# Seeeduino-Stalker-v3_0.net
KiCad netlist of a schematic drawn in EAGLE
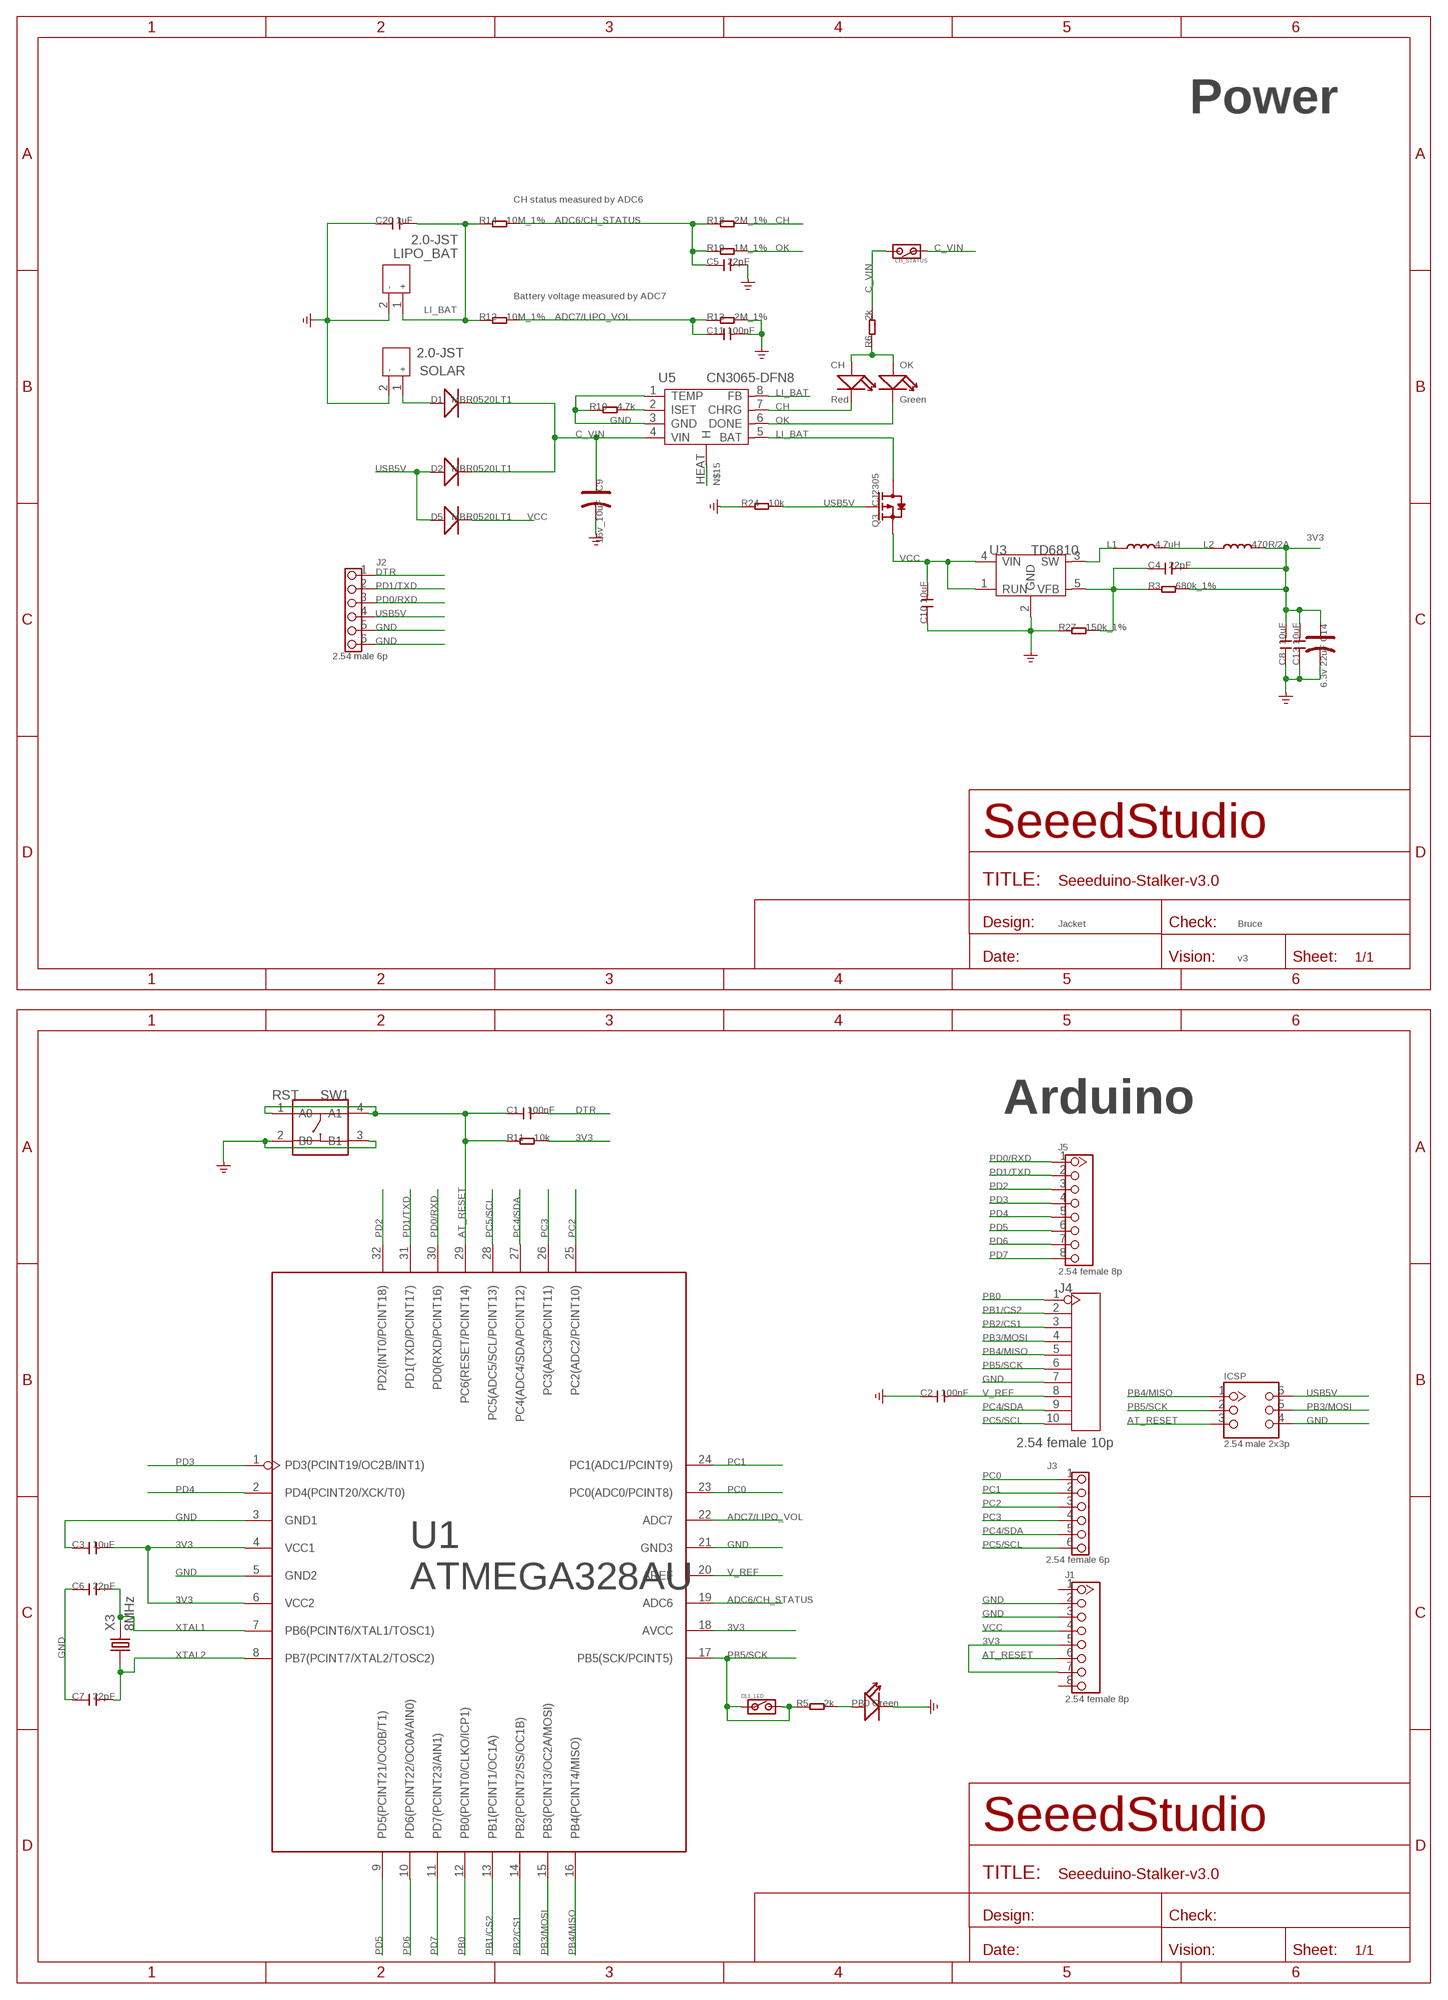
[diagram p0: schematic, sheet 1, part 1 of 2]
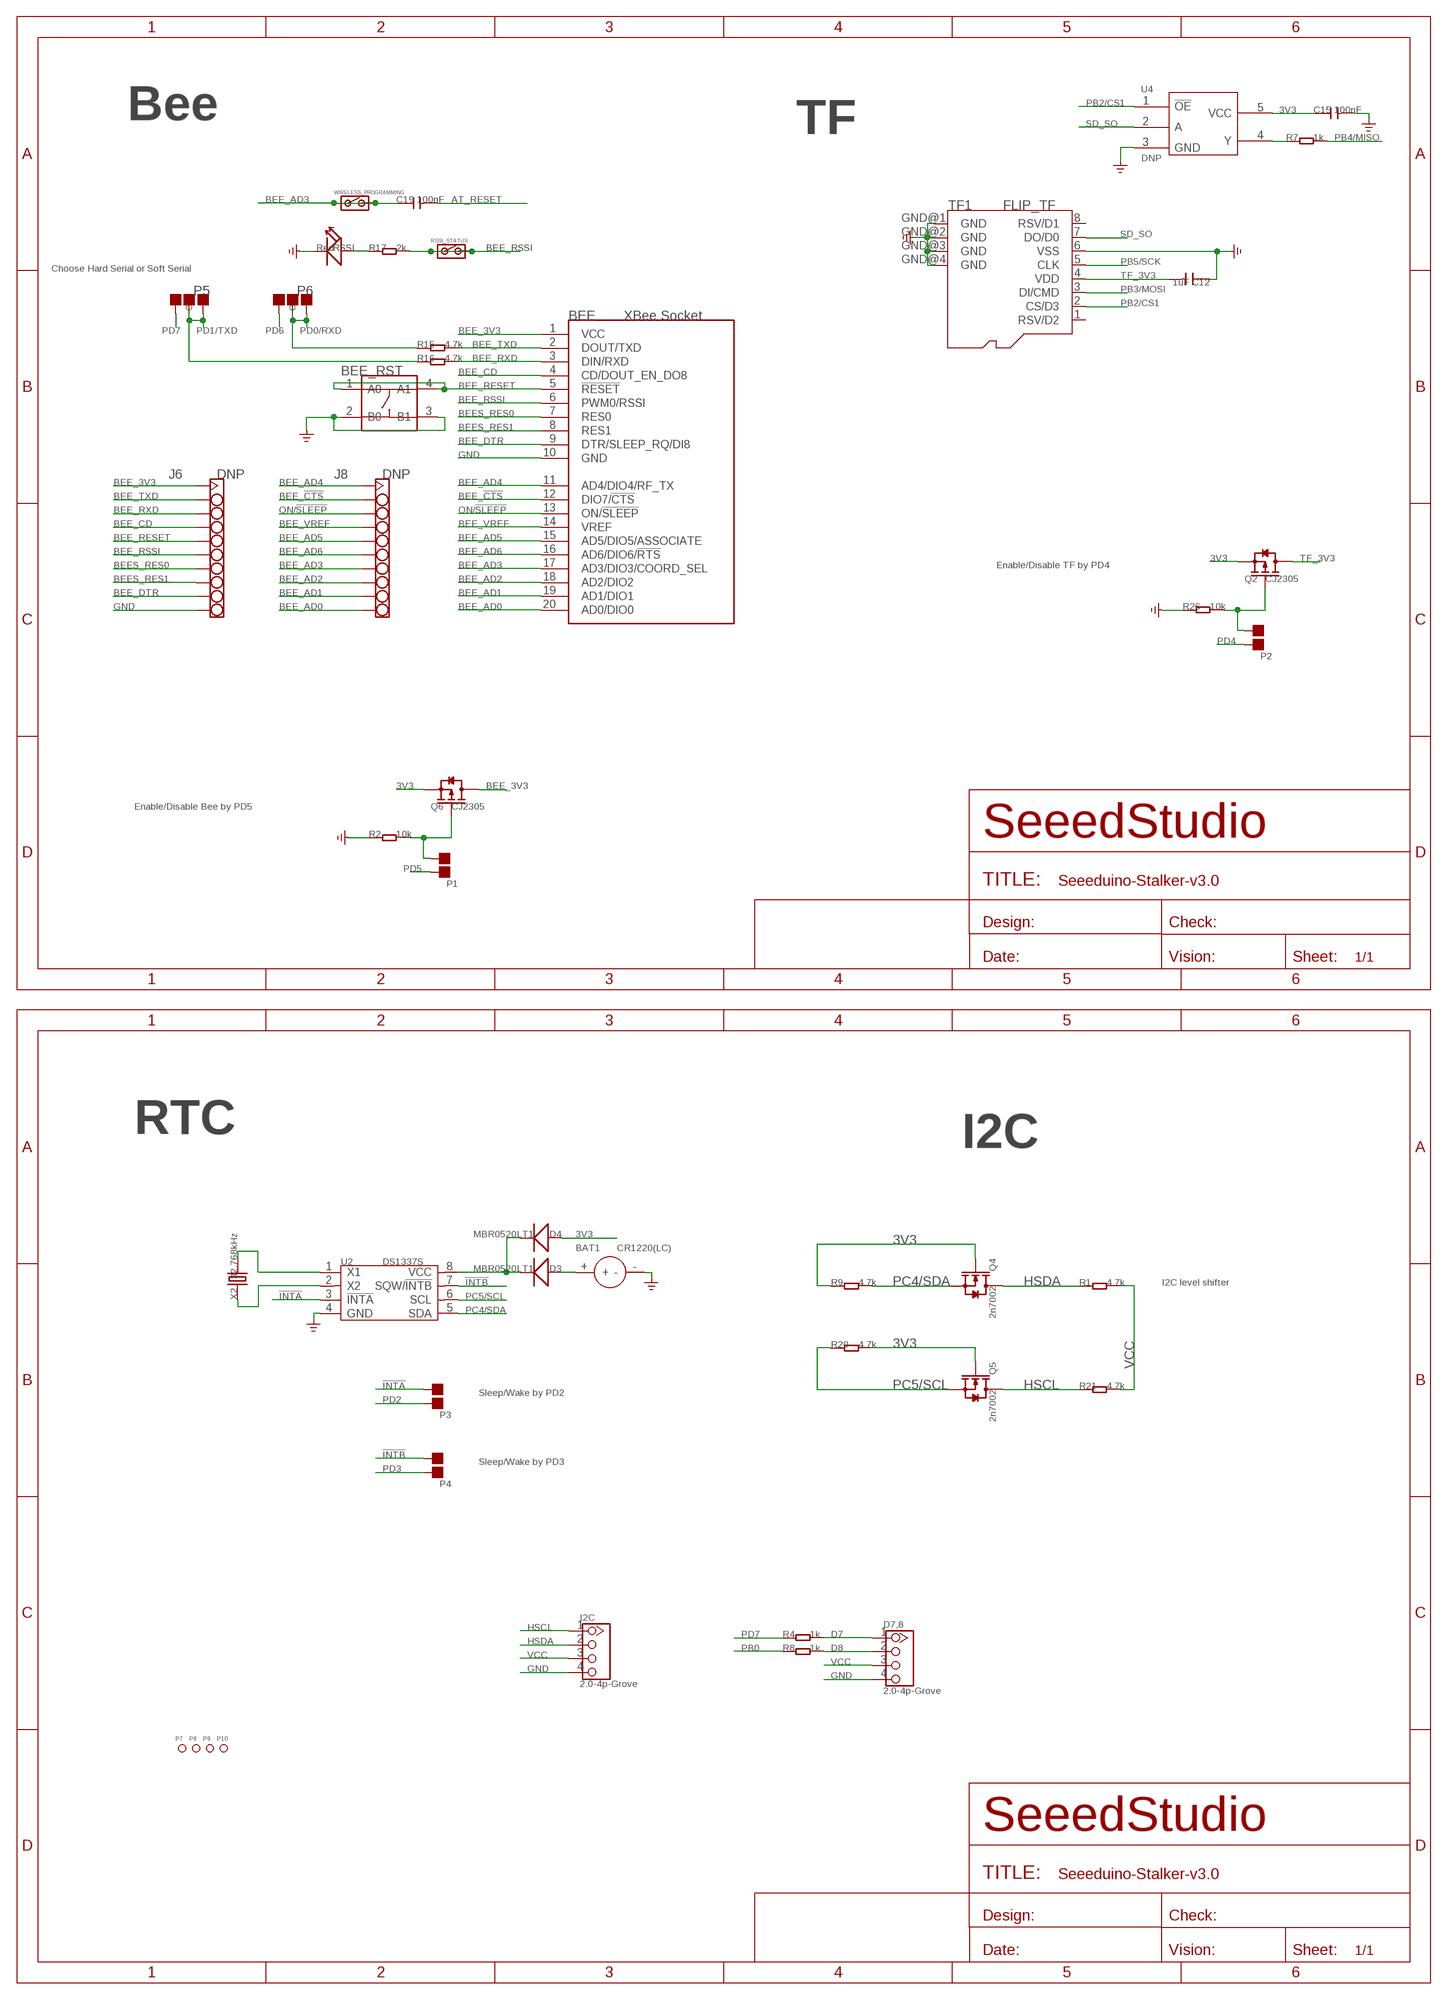
[diagram p1: schematic, sheet 1, part 2 of 2]

(export (version "E")
  (design (tool "Eeschema 10.0.6"))
  (components
    (comp (ref "BAT1")
      (value "CR1220(LC)")
      (footprint "eagle-import:2P-D12.55X2.22H")
      (libsource (lib "eagle-import") (part "BATTERY-3V"))
    )
    (comp (ref "BEE")
      (value "XBee Socket")
      (footprint "eagle-import:BEE")
      (libsource (lib "eagle-import") (part "BEEO"))
    )
    (comp (ref "BEE_RST")
      (value "SW2")
      (footprint "eagle-import:4P-SMD-6.2X6.2X4H")
      (libsource (lib "eagle-import") (part "BUTTON-4P-6X6-SMD"))
    )
    (comp (ref "C1")
      (value "100nF")
      (footprint "eagle-import:C0603")
      (libsource (lib "eagle-import") (part "C-0603"))
    )
    (comp (ref "C2")
      (value "100nF")
      (footprint "eagle-import:C0603")
      (libsource (lib "eagle-import") (part "C-0603"))
    )
    (comp (ref "C3")
      (value "10uF")
      (footprint "eagle-import:C0805")
      (libsource (lib "eagle-import") (part "C-0805"))
    )
    (comp (ref "C4")
      (value "22pF")
      (footprint "eagle-import:C0603")
      (libsource (lib "eagle-import") (part "C-0603"))
    )
    (comp (ref "C5")
      (value "22pF")
      (footprint "eagle-import:C0603")
      (libsource (lib "eagle-import") (part "C-0603"))
    )
    (comp (ref "C6")
      (value "22pF")
      (footprint "eagle-import:C0603")
      (libsource (lib "eagle-import") (part "C-0603"))
    )
    (comp (ref "C7")
      (value "22pF")
      (footprint "eagle-import:C0603")
      (libsource (lib "eagle-import") (part "C-0603"))
    )
    (comp (ref "C8")
      (value "10uF")
      (footprint "eagle-import:C0805")
      (libsource (lib "eagle-import") (part "C-0805"))
    )
    (comp (ref "C9")
      (value "16v_10uF")
      (footprint "eagle-import:AVX-A")
      (libsource (lib "eagle-import") (part "CAP-AVX-A"))
    )
    (comp (ref "C10")
      (value "10uF")
      (footprint "eagle-import:C0805")
      (libsource (lib "eagle-import") (part "C-0805"))
    )
    (comp (ref "C11")
      (value "100nF")
      (footprint "eagle-import:C0603")
      (libsource (lib "eagle-import") (part "C-0603"))
    )
    (comp (ref "C12")
      (value "1uF")
      (footprint "eagle-import:C0805")
      (libsource (lib "eagle-import") (part "C-0805"))
    )
    (comp (ref "C13")
      (value "10uF")
      (footprint "eagle-import:C0805")
      (libsource (lib "eagle-import") (part "C-0805"))
    )
    (comp (ref "C14")
      (value "6.3v 22uF")
      (footprint "eagle-import:AVX-A")
      (libsource (lib "eagle-import") (part "CAP-AVX-A"))
    )
    (comp (ref "C15")
      (value "100nF")
      (footprint "eagle-import:C0603")
      (libsource (lib "eagle-import") (part "C-0603"))
    )
    (comp (ref "C19")
      (value "100nF")
      (footprint "eagle-import:C0603")
      (libsource (lib "eagle-import") (part "C-0603"))
    )
    (comp (ref "C20")
      (value "1uF")
      (footprint "eagle-import:C0805")
      (libsource (lib "eagle-import") (part "C-0805"))
    )
    (comp (ref "CH")
      (value "Red")
      (footprint "eagle-import:D0603")
      (libsource (lib "eagle-import") (part "007-LED0603"))
    )
    (comp (ref "CH_STATUS")
      (value "DNP")
      (footprint "eagle-import:JP_SW")
      (libsource (lib "eagle-import") (part "JP_SW"))
    )
    (comp (ref "D1")
      (value "MBR0520LT1")
      (footprint "eagle-import:SOD123-2.7X1.6")
      (libsource (lib "eagle-import") (part "D'MBR0520LT1'"))
    )
    (comp (ref "D2")
      (value "MBR0520LT1")
      (footprint "eagle-import:SOD123-2.7X1.6")
      (libsource (lib "eagle-import") (part "D'MBR0520LT1'"))
    )
    (comp (ref "D3")
      (value "MBR0520LT1")
      (footprint "eagle-import:SOD123-2.7X1.6")
      (libsource (lib "eagle-import") (part "D'MBR0520LT1'"))
    )
    (comp (ref "D4")
      (value "MBR0520LT1")
      (footprint "eagle-import:SOD123-2.7X1.6")
      (libsource (lib "eagle-import") (part "D'MBR0520LT1'"))
    )
    (comp (ref "D5")
      (value "MBR0520LT1")
      (footprint "eagle-import:SOD123-2.7X1.6")
      (libsource (lib "eagle-import") (part "D'MBR0520LT1'"))
    )
    (comp (ref "D7,8")
      (value "2.0-4p-Grove")
      (footprint "eagle-import:4P-2.0")
      (libsource (lib "eagle-import") (part "TWIG-4P-2.0-2.0"))
    )
    (comp (ref "D13_LED")
      (value "DNP")
      (footprint "eagle-import:JP_SW")
      (libsource (lib "eagle-import") (part "JP_SW"))
    )
    (comp (ref "I2C")
      (value "2.0-4p-Grove")
      (footprint "eagle-import:4P-2.0")
      (libsource (lib "eagle-import") (part "TWIG-4P-2.0-2.0"))
    )
    (comp (ref "ICSP")
      (value "2.54 male 2x3p")
      (footprint "eagle-import:2X3P-2.54-LEADED")
      (libsource (lib "eagle-import") (part "HEADER-2X3P-2.54"))
    )
    (comp (ref "J1")
      (value "2.54 female 8p")
      (footprint "eagle-import:8P-2.54-LEADED")
      (libsource (lib "eagle-import") (part "HEADER-8P-2.54-LEADED"))
    )
    (comp (ref "J2")
      (value "2.54 male 6p")
      (footprint "eagle-import:6P-2.54-LEADED")
      (libsource (lib "eagle-import") (part "HEADER-6P-LEADED-2.54"))
    )
    (comp (ref "J3")
      (value "2.54 female 6p")
      (footprint "eagle-import:6P-2.54-LEADED")
      (libsource (lib "eagle-import") (part "HEADER-6P-LEADED-2.54"))
    )
    (comp (ref "J4")
      (value "2.54 female 10p")
      (footprint "eagle-import:10P-2.54")
      (libsource (lib "eagle-import") (part "HEADER-10P-2.54"))
    )
    (comp (ref "J5")
      (value "2.54 female 8p")
      (footprint "eagle-import:8P-2.54-LEADED")
      (libsource (lib "eagle-import") (part "HEADER-8P-2.54-LEADED"))
    )
    (comp (ref "J6")
      (value "DNP")
      (footprint "eagle-import:HEADER_1X10")
      (libsource (lib "eagle-import") (part "HEADER_1X10DD"))
    )
    (comp (ref "J8")
      (value "DNP")
      (footprint "eagle-import:HEADER_1X10")
      (libsource (lib "eagle-import") (part "HEADER_1X10DD"))
    )
    (comp (ref "L1")
      (value "4.7uH")
      (footprint "eagle-import:L0420")
      (libsource (lib "eagle-import") (part "LSPD3D16-4R7M"))
    )
    (comp (ref "L2")
      (value "470R/2A")
      (footprint "eagle-import:L0805")
      (libsource (lib "eagle-import") (part "L'0805'"))
    )
    (comp (ref "LIPO_BAT")
      (value "2.0-JST")
      (footprint "eagle-import:JST-2.0")
      (libsource (lib "eagle-import") (part "JACK-JST-2P-PW'2.0'"))
    )
    (comp (ref "OK")
      (value "Green")
      (footprint "eagle-import:D0603")
      (libsource (lib "eagle-import") (part "007-LED0603"))
    )
    (comp (ref "P1")
      (value "DNP")
      (footprint "eagle-import:2P-SMD-1.78X1.27")
      (libsource (lib "eagle-import") (part "PAD-JUMPER-2P"))
    )
    (comp (ref "P2")
      (value "DNP")
      (footprint "eagle-import:2P-SMD-1.78X1.27")
      (libsource (lib "eagle-import") (part "PAD-JUMPER-2P"))
    )
    (comp (ref "P3")
      (value "DNP")
      (footprint "eagle-import:2P-SMD-1.78X1.27")
      (libsource (lib "eagle-import") (part "PAD-JUMPER-2P"))
    )
    (comp (ref "P4")
      (value "DNP")
      (footprint "eagle-import:2P-SMD-1.78X1.27")
      (libsource (lib "eagle-import") (part "PAD-JUMPER-2P"))
    )
    (comp (ref "P5")
      (value "DNP")
      (footprint "eagle-import:3P-SMD-4.1X1.5")
      (libsource (lib "eagle-import") (part "PAD-JUMPER-3P-4040"))
    )
    (comp (ref "P6")
      (value "DNP")
      (footprint "eagle-import:3P-SMD-4.1X1.5")
      (libsource (lib "eagle-import") (part "PAD-JUMPER-3P-4040"))
    )
    (comp (ref "P7")
      (value "PAD-MARK")
      (footprint "eagle-import:ROUND-MARK-1.0")
      (fields (field (name "PARTNO") "DNP"))
      (libsource (lib "eagle-import") (part "PAD-MARK"))
    )
    (comp (ref "P8")
      (value "PAD-MARK")
      (footprint "eagle-import:ROUND-MARK-1.0")
      (fields (field (name "PARTNO") "DNP"))
      (libsource (lib "eagle-import") (part "PAD-MARK"))
    )
    (comp (ref "P9")
      (value "PAD-MARK")
      (footprint "eagle-import:ROUND-MARK-1.0")
      (fields (field (name "PARTNO") "DNP"))
      (libsource (lib "eagle-import") (part "PAD-MARK"))
    )
    (comp (ref "P10")
      (value "PAD-MARK")
      (footprint "eagle-import:ROUND-MARK-1.0")
      (fields (field (name "PARTNO") "DNP"))
      (libsource (lib "eagle-import") (part "PAD-MARK"))
    )
    (comp (ref "PB0")
      (value "Green")
      (footprint "eagle-import:D0603")
      (libsource (lib "eagle-import") (part "007-LED0603"))
    )
    (comp (ref "Q2")
      (value "CJ2305")
      (footprint "eagle-import:SOT23")
      (libsource (lib "eagle-import") (part "MOSFET-P'SI2323CDS/SI2305DS{lt}BR{gt}'"))
    )
    (comp (ref "Q3")
      (value "CJ2305")
      (footprint "eagle-import:SOT23")
      (libsource (lib "eagle-import") (part "MOSFET-P'SI2323CDS/SI2305DS{lt}BR{gt}'"))
    )
    (comp (ref "Q4")
      (value "2n7002")
      (footprint "eagle-import:SOT23")
      (libsource (lib "eagle-import") (part "MOSFET-N'SOT23'"))
    )
    (comp (ref "Q5")
      (value "2n7002")
      (footprint "eagle-import:SOT23")
      (libsource (lib "eagle-import") (part "MOSFET-N'SOT23'"))
    )
    (comp (ref "Q6")
      (value "CJ2305")
      (footprint "eagle-import:SOT23")
      (libsource (lib "eagle-import") (part "MOSFET-P'SI2323CDS/SI2305DS{lt}BR{gt}'"))
    )
    (comp (ref "R1")
      (value "4.7k")
      (footprint "eagle-import:0603@1")
      (libsource (lib "eagle-import") (part "005-R0603"))
    )
    (comp (ref "R2")
      (value "10k")
      (footprint "eagle-import:0603@1")
      (libsource (lib "eagle-import") (part "005-R0603"))
    )
    (comp (ref "R3")
      (value "680k_1%")
      (footprint "eagle-import:0603@1")
      (libsource (lib "eagle-import") (part "005-R0603"))
    )
    (comp (ref "R4")
      (value "1k")
      (footprint "eagle-import:0603@1")
      (libsource (lib "eagle-import") (part "005-R0603"))
    )
    (comp (ref "R5")
      (value "2k")
      (footprint "eagle-import:0603@1")
      (libsource (lib "eagle-import") (part "005-R0603"))
    )
    (comp (ref "R6")
      (value "2k")
      (footprint "eagle-import:0603@1")
      (libsource (lib "eagle-import") (part "005-R0603"))
    )
    (comp (ref "R7")
      (value "1k")
      (footprint "eagle-import:0603@1")
      (libsource (lib "eagle-import") (part "005-R0603"))
    )
    (comp (ref "R8")
      (value "1k")
      (footprint "eagle-import:0603@1")
      (libsource (lib "eagle-import") (part "005-R0603"))
    )
    (comp (ref "R9")
      (value "4.7k")
      (footprint "eagle-import:0603@1")
      (libsource (lib "eagle-import") (part "005-R0603"))
    )
    (comp (ref "R10")
      (value "4.7k")
      (footprint "eagle-import:0603@1")
      (libsource (lib "eagle-import") (part "005-R0603"))
    )
    (comp (ref "R11")
      (value "10k")
      (footprint "eagle-import:0603@1")
      (libsource (lib "eagle-import") (part "005-R0603"))
    )
    (comp (ref "R12")
      (value "10M_1%")
      (footprint "eagle-import:0603@1")
      (libsource (lib "eagle-import") (part "005-R0603"))
    )
    (comp (ref "R13")
      (value "2M_1%")
      (footprint "eagle-import:0603@1")
      (libsource (lib "eagle-import") (part "005-R0603"))
    )
    (comp (ref "R14")
      (value "10M_1%")
      (footprint "eagle-import:0603@1")
      (libsource (lib "eagle-import") (part "005-R0603"))
    )
    (comp (ref "R15")
      (value "4.7k")
      (footprint "eagle-import:0603@1")
      (libsource (lib "eagle-import") (part "005-R0603"))
    )
    (comp (ref "R16")
      (value "4.7k")
      (footprint "eagle-import:0603@1")
      (libsource (lib "eagle-import") (part "005-R0603"))
    )
    (comp (ref "R17")
      (value "2k")
      (footprint "eagle-import:0603@1")
      (libsource (lib "eagle-import") (part "005-R0603"))
    )
    (comp (ref "R18")
      (value "2M_1%")
      (footprint "eagle-import:0603@1")
      (libsource (lib "eagle-import") (part "005-R0603"))
    )
    (comp (ref "R19")
      (value "1M_1%")
      (footprint "eagle-import:0603@1")
      (libsource (lib "eagle-import") (part "005-R0603"))
    )
    (comp (ref "R20")
      (value "4.7k")
      (footprint "eagle-import:0603@1")
      (libsource (lib "eagle-import") (part "005-R0603"))
    )
    (comp (ref "R21")
      (value "4.7k")
      (footprint "eagle-import:0603@1")
      (libsource (lib "eagle-import") (part "005-R0603"))
    )
    (comp (ref "R24")
      (value "10k")
      (footprint "eagle-import:0603@1")
      (libsource (lib "eagle-import") (part "005-R0603"))
    )
    (comp (ref "R26")
      (value "10k")
      (footprint "eagle-import:0603@1")
      (libsource (lib "eagle-import") (part "005-R0603"))
    )
    (comp (ref "R27")
      (value "150k_1%")
      (footprint "eagle-import:0603@1")
      (libsource (lib "eagle-import") (part "005-R0603"))
    )
    (comp (ref "RSSI")
      (value "Red")
      (footprint "eagle-import:D0603")
      (libsource (lib "eagle-import") (part "007-LED0603"))
    )
    (comp (ref "RSSI_STATUS")
      (value "DNP")
      (footprint "eagle-import:JP_SW")
      (libsource (lib "eagle-import") (part "JP_SW"))
    )
    (comp (ref "RST")
      (value "SW1")
      (footprint "eagle-import:4P-SMD-6.2X6.2X4H")
      (libsource (lib "eagle-import") (part "BUTTON-4P-6X6-SMD"))
    )
    (comp (ref "SOLAR")
      (value "2.0-JST")
      (footprint "eagle-import:JST-2.0")
      (libsource (lib "eagle-import") (part "JACK-JST-2P-PW'2.0'"))
    )
    (comp (ref "TF1")
      (value "FLIP_TF")
      (footprint "eagle-import:FLIP_TF")
      (libsource (lib "eagle-import") (part "FLIP_TF"))
    )
    (comp (ref "U1")
      (value "ATMEGA328AU")
      (footprint "eagle-import:ATMEGA168-20AU")
      (libsource (lib "eagle-import") (part "ATMEGA168-20AU"))
    )
    (comp (ref "U2")
      (value "DS1337S")
      (footprint "eagle-import:SOP8")
      (libsource (lib "eagle-import") (part "DS1337S"))
    )
    (comp (ref "U3")
      (value "TD6810")
      (footprint "eagle-import:SOT23-5")
      (libsource (lib "eagle-import") (part "TD6810'TSOT23-5'"))
    )
    (comp (ref "U4")
      (value "DNP")
      (footprint "eagle-import:SOT353")
      (libsource (lib "eagle-import") (part "SN74LVC1G125DCKR"))
    )
    (comp (ref "U5")
      (value "CN3065-DFN8")
      (footprint "eagle-import:DFN8")
      (libsource (lib "eagle-import") (part "CN3065-DFN8"))
    )
    (comp (ref "WIRELESS_PROGRAMMING")
      (value "DNP")
      (footprint "eagle-import:JP_SW")
      (libsource (lib "eagle-import") (part "JP_SW"))
    )
    (comp (ref "X2")
      (value "32.768kHz")
      (footprint "eagle-import:2P-SMD-3.2X1.5")
      (libsource (lib "eagle-import") (part "CRYSTAL-3215"))
    )
    (comp (ref "X3")
      (value "8MHz")
      (footprint "eagle-import:HC49_S")
      (libsource (lib "eagle-import") (part "011-CRYSTALHC49S"))
    )
  )
  (nets
    (net (code "1") (name "/3V3") (class "Default")
      (node (ref "C13") (pin "2") (pinfunction "2_2") (pintype "passive"))
      (node (ref "C14") (pin "+") (pinfunction "+_+") (pintype "passive"))
      (node (ref "C15") (pin "1") (pinfunction "1_1") (pintype "passive"))
      (node (ref "C3") (pin "2") (pinfunction "2_2") (pintype "passive"))
      (node (ref "C4") (pin "2") (pinfunction "2_2") (pintype "passive"))
      (node (ref "C8") (pin "2") (pinfunction "2_2") (pintype "passive"))
      (node (ref "D4") (pin "1") (pinfunction "+_1") (pintype "passive"))
      (node (ref "J1") (pin "5") (pinfunction "5_5") (pintype "bidirectional"))
      (node (ref "J1") (pin "7") (pinfunction "7_7") (pintype "bidirectional"))
      (node (ref "L2") (pin "2") (pinfunction "2_2") (pintype "passive"))
      (node (ref "Q2") (pin "2") (pinfunction "S_2") (pintype "passive"))
      (node (ref "Q4") (pin "1") (pinfunction "G_1") (pintype "passive"))
      (node (ref "Q5") (pin "1") (pinfunction "G_1") (pintype "passive"))
      (node (ref "Q6") (pin "2") (pinfunction "S_2") (pintype "passive"))
      (node (ref "R11") (pin "2") (pinfunction "2_2") (pintype "passive"))
      (node (ref "R20") (pin "2") (pinfunction "2_2") (pintype "passive"))
      (node (ref "R3") (pin "2") (pinfunction "2_2") (pintype "passive"))
      (node (ref "R9") (pin "1") (pinfunction "1_1") (pintype "passive"))
      (node (ref "U1") (pin "18") (pinfunction "AVCC_18") (pintype "bidirectional"))
      (node (ref "U1") (pin "4") (pinfunction "VCC1_4") (pintype "bidirectional"))
      (node (ref "U1") (pin "6") (pinfunction "VCC2_6") (pintype "bidirectional"))
      (node (ref "U4") (pin "5") (pinfunction "VCC_5") (pintype "bidirectional"))
    )
    (net (code "2") (name "/ADC6{slash}CH_STATUS") (class "Default")
      (node (ref "C5") (pin "1") (pinfunction "1_1") (pintype "passive"))
      (node (ref "R14") (pin "2") (pinfunction "2_2") (pintype "passive"))
      (node (ref "R18") (pin "1") (pinfunction "1_1") (pintype "passive"))
      (node (ref "R19") (pin "1") (pinfunction "1_1") (pintype "passive"))
      (node (ref "U1") (pin "19") (pinfunction "ADC6_19") (pintype "bidirectional"))
    )
    (net (code "3") (name "/ADC7{slash}LIPO_VOL") (class "Default")
      (node (ref "C11") (pin "1") (pinfunction "1_1") (pintype "passive"))
      (node (ref "R12") (pin "2") (pinfunction "2_2") (pintype "passive"))
      (node (ref "R13") (pin "1") (pinfunction "1_1") (pintype "passive"))
      (node (ref "U1") (pin "22") (pinfunction "ADC7_22") (pintype "bidirectional"))
    )
    (net (code "4") (name "/AT_RESET") (class "Default")
      (node (ref "C1") (pin "1") (pinfunction "1_1") (pintype "passive"))
      (node (ref "C19") (pin "2") (pinfunction "2_2") (pintype "passive"))
      (node (ref "ICSP") (pin "3") (pinfunction "3_3") (pintype "bidirectional"))
      (node (ref "J1") (pin "6") (pinfunction "6_6") (pintype "bidirectional"))
      (node (ref "R11") (pin "1") (pinfunction "1_1") (pintype "passive"))
      (node (ref "RST") (pin "1") (pinfunction "A0_1") (pintype "bidirectional"))
      (node (ref "RST") (pin "4") (pinfunction "A1_4") (pintype "bidirectional"))
      (node (ref "U1") (pin "29") (pinfunction "PC6(RESET/PCINT14)_29") (pintype "bidirectional"))
    )
    (net (code "5") (name "/BEES_RES0") (class "Default")
      (node (ref "BEE") (pin "7") (pinfunction "RES0_7") (pintype "bidirectional"))
      (node (ref "J6") (pin "7") (pinfunction "7_7") (pintype "bidirectional"))
    )
    (net (code "6") (name "/BEES_RES1") (class "Default")
      (node (ref "BEE") (pin "8") (pinfunction "RES1_8") (pintype "bidirectional"))
      (node (ref "J6") (pin "8") (pinfunction "8_8") (pintype "bidirectional"))
    )
    (net (code "7") (name "/BEE_3V3") (class "Default")
      (node (ref "BEE") (pin "1") (pinfunction "VCC_1") (pintype "bidirectional"))
      (node (ref "J6") (pin "1") (pinfunction "1_1") (pintype "bidirectional"))
      (node (ref "Q6") (pin "3") (pinfunction "D_3") (pintype "passive"))
    )
    (net (code "8") (name "/BEE_AD0") (class "Default")
      (node (ref "BEE") (pin "20") (pinfunction "AD0/DIO0_20") (pintype "bidirectional"))
      (node (ref "J8") (pin "10") (pinfunction "10_10") (pintype "bidirectional"))
    )
    (net (code "9") (name "/BEE_AD1") (class "Default")
      (node (ref "BEE") (pin "19") (pinfunction "AD1/DIO1_19") (pintype "bidirectional"))
      (node (ref "J8") (pin "9") (pinfunction "9_9") (pintype "bidirectional"))
    )
    (net (code "10") (name "/BEE_AD2") (class "Default")
      (node (ref "BEE") (pin "18") (pinfunction "AD2/DIO2_18") (pintype "bidirectional"))
      (node (ref "J8") (pin "8") (pinfunction "8_8") (pintype "bidirectional"))
    )
    (net (code "11") (name "/BEE_AD3") (class "Default")
      (node (ref "BEE") (pin "17") (pinfunction "AD3/DIO3/COORD_SEL_17") (pintype "bidirectional"))
      (node (ref "C19") (pin "1") (pinfunction "1_1") (pintype "passive"))
      (node (ref "J8") (pin "7") (pinfunction "7_7") (pintype "bidirectional"))
      (node (ref "WIRELESS_PROGRAMMING") (pin "1") (pinfunction "1_1") (pintype "bidirectional"))
      (node (ref "WIRELESS_PROGRAMMING") (pin "2") (pinfunction "2_2") (pintype "bidirectional"))
    )
    (net (code "12") (name "/BEE_AD4") (class "Default")
      (node (ref "BEE") (pin "11") (pinfunction "AD4/DIO4/RF_TX_11") (pintype "bidirectional"))
      (node (ref "J8") (pin "1") (pinfunction "1_1") (pintype "bidirectional"))
    )
    (net (code "13") (name "/BEE_AD5") (class "Default")
      (node (ref "BEE") (pin "15") (pinfunction "AD5/DIO5/ASSOCIATE_15") (pintype "bidirectional"))
      (node (ref "J8") (pin "5") (pinfunction "5_5") (pintype "bidirectional"))
    )
    (net (code "14") (name "/BEE_AD6") (class "Default")
      (node (ref "BEE") (pin "16") (pinfunction "AD6/DIO6/~{RTS}_16") (pintype "bidirectional"))
      (node (ref "J8") (pin "6") (pinfunction "6_6") (pintype "bidirectional"))
    )
    (net (code "15") (name "/BEE_CD") (class "Default")
      (node (ref "BEE") (pin "4") (pinfunction "CD/DOUT_EN_DO8_4") (pintype "bidirectional"))
      (node (ref "J6") (pin "4") (pinfunction "4_4") (pintype "bidirectional"))
    )
    (net (code "16") (name "/BEE_DTR") (class "Default")
      (node (ref "BEE") (pin "9") (pinfunction "DTR/SLEEP_RQ/DI8_9") (pintype "bidirectional"))
      (node (ref "J6") (pin "9") (pinfunction "9_9") (pintype "bidirectional"))
    )
    (net (code "17") (name "/BEE_RESET") (class "Default")
      (node (ref "BEE") (pin "5") (pinfunction "~{RESET}_5") (pintype "bidirectional"))
      (node (ref "BEE_RST") (pin "1") (pinfunction "A0_1") (pintype "bidirectional"))
      (node (ref "BEE_RST") (pin "4") (pinfunction "A1_4") (pintype "bidirectional"))
      (node (ref "J6") (pin "5") (pinfunction "5_5") (pintype "bidirectional"))
    )
    (net (code "18") (name "/BEE_RSSI") (class "Default")
      (node (ref "BEE") (pin "6") (pinfunction "PWM0/RSSI_6") (pintype "bidirectional"))
      (node (ref "J6") (pin "6") (pinfunction "6_6") (pintype "bidirectional"))
      (node (ref "R17") (pin "2") (pinfunction "2_2") (pintype "passive"))
      (node (ref "RSSI_STATUS") (pin "1") (pinfunction "1_1") (pintype "bidirectional"))
      (node (ref "RSSI_STATUS") (pin "2") (pinfunction "2_2") (pintype "bidirectional"))
    )
    (net (code "19") (name "/BEE_RXD") (class "Default")
      (node (ref "BEE") (pin "3") (pinfunction "DIN/RXD_3") (pintype "bidirectional"))
      (node (ref "J6") (pin "3") (pinfunction "3_3") (pintype "bidirectional"))
      (node (ref "R16") (pin "2") (pinfunction "2_2") (pintype "passive"))
    )
    (net (code "20") (name "/BEE_TXD") (class "Default")
      (node (ref "BEE") (pin "2") (pinfunction "DOUT/TXD_2") (pintype "bidirectional"))
      (node (ref "J6") (pin "2") (pinfunction "2_2") (pintype "bidirectional"))
      (node (ref "R15") (pin "2") (pinfunction "2_2") (pintype "passive"))
    )
    (net (code "21") (name "/BEE_VREF") (class "Default")
      (node (ref "BEE") (pin "14") (pinfunction "VREF_14") (pintype "bidirectional"))
      (node (ref "J8") (pin "4") (pinfunction "4_4") (pintype "bidirectional"))
    )
    (net (code "22") (name "/BEE_~{CTS}") (class "Default")
      (node (ref "BEE") (pin "12") (pinfunction "DIO7/~{CTS}_12") (pintype "bidirectional"))
      (node (ref "J8") (pin "2") (pinfunction "2_2") (pintype "bidirectional"))
    )
    (net (code "23") (name "/CH") (class "Default")
      (node (ref "CH") (pin "-") (pinfunction "-_-") (pintype "passive"))
      (node (ref "R18") (pin "2") (pinfunction "2_2") (pintype "passive"))
      (node (ref "U5") (pin "7") (pinfunction "CHRG_7") (pintype "bidirectional"))
    )
    (net (code "24") (name "/C_VIN") (class "Default")
      (node (ref "C9") (pin "+") (pinfunction "+_+") (pintype "passive"))
      (node (ref "CH_STATUS") (pin "1") (pinfunction "1_1") (pintype "bidirectional"))
      (node (ref "CH_STATUS") (pin "2") (pinfunction "2_2") (pintype "bidirectional"))
      (node (ref "D1") (pin "2") (pinfunction "-_2") (pintype "passive"))
      (node (ref "D2") (pin "2") (pinfunction "-_2") (pintype "passive"))
      (node (ref "R6") (pin "2") (pinfunction "2_2") (pintype "passive"))
      (node (ref "U5") (pin "4") (pinfunction "VIN_4") (pintype "input"))
    )
    (net (code "25") (name "/D7") (class "Default")
      (node (ref "D7,8") (pin "1") (pinfunction "1_1") (pintype "bidirectional"))
      (node (ref "R4") (pin "2") (pinfunction "2_2") (pintype "passive"))
    )
    (net (code "26") (name "/D8") (class "Default")
      (node (ref "D7,8") (pin "2") (pinfunction "2_2") (pintype "bidirectional"))
      (node (ref "R8") (pin "2") (pinfunction "2_2") (pintype "passive"))
    )
    (net (code "27") (name "/DTR") (class "Default")
      (node (ref "C1") (pin "2") (pinfunction "2_2") (pintype "passive"))
      (node (ref "J2") (pin "1") (pinfunction "1_1") (pintype "bidirectional"))
    )
    (net (code "28") (name "/HSCL") (class "Default")
      (node (ref "I2C") (pin "1") (pinfunction "1_1") (pintype "bidirectional"))
      (node (ref "Q5") (pin "3") (pinfunction "D_3") (pintype "passive"))
      (node (ref "R21") (pin "1") (pinfunction "1_1") (pintype "passive"))
    )
    (net (code "29") (name "/HSDA") (class "Default")
      (node (ref "I2C") (pin "2") (pinfunction "2_2") (pintype "bidirectional"))
      (node (ref "Q4") (pin "3") (pinfunction "D_3") (pintype "passive"))
      (node (ref "R1") (pin "1") (pinfunction "1_1") (pintype "passive"))
    )
    (net (code "30") (name "/LI_BAT") (class "Default")
      (node (ref "C20") (pin "2") (pinfunction "2_2") (pintype "passive"))
      (node (ref "LIPO_BAT") (pin "1") (pinfunction "P$1_1") (pintype "bidirectional"))
      (node (ref "Q3") (pin "3") (pinfunction "D_3") (pintype "passive"))
      (node (ref "R12") (pin "1") (pinfunction "1_1") (pintype "passive"))
      (node (ref "R14") (pin "1") (pinfunction "1_1") (pintype "passive"))
      (node (ref "U5") (pin "5") (pinfunction "BAT_5") (pintype "bidirectional"))
      (node (ref "U5") (pin "8") (pinfunction "FB_8") (pintype "input"))
    )
    (net (code "31") (name "/N$15") (class "Default")
      (node (ref "U5") (pin "HEAT") (pinfunction "H_HEAT") (pintype "bidirectional"))
    )
    (net (code "32") (name "/OK") (class "Default")
      (node (ref "OK") (pin "-") (pinfunction "-_-") (pintype "passive"))
      (node (ref "R19") (pin "2") (pinfunction "2_2") (pintype "passive"))
      (node (ref "U5") (pin "6") (pinfunction "DONE_6") (pintype "bidirectional"))
    )
    (net (code "33") (name "/ON{slash}~{SLEEP}") (class "Default")
      (node (ref "BEE") (pin "13") (pinfunction "ON/~{SLEEP}_13") (pintype "bidirectional"))
      (node (ref "J8") (pin "3") (pinfunction "3_3") (pintype "bidirectional"))
    )
    (net (code "34") (name "/PB0") (class "Default")
      (node (ref "J4") (pin "1") (pinfunction "1_1") (pintype "bidirectional"))
      (node (ref "R8") (pin "1") (pinfunction "1_1") (pintype "passive"))
      (node (ref "U1") (pin "12") (pinfunction "PB0(PCINT0/CLKO/ICP1)_12") (pintype "bidirectional"))
    )
    (net (code "35") (name "/PB1{slash}CS2") (class "Default")
      (node (ref "J4") (pin "2") (pinfunction "2_2") (pintype "bidirectional"))
      (node (ref "U1") (pin "13") (pinfunction "PB1(PCINT1/OC1A)_13") (pintype "bidirectional"))
    )
    (net (code "36") (name "/PB2{slash}CS1") (class "Default")
      (node (ref "J4") (pin "3") (pinfunction "3_3") (pintype "bidirectional"))
      (node (ref "TF1") (pin "2") (pinfunction "CS/D3_2") (pintype "bidirectional"))
      (node (ref "U1") (pin "14") (pinfunction "PB2(PCINT2/SS/OC1B)_14") (pintype "bidirectional"))
      (node (ref "U4") (pin "1") (pinfunction "~{OE}_1") (pintype "bidirectional"))
    )
    (net (code "37") (name "/PB3{slash}MOSI") (class "Default")
      (node (ref "ICSP") (pin "5") (pinfunction "5_5") (pintype "bidirectional"))
      (node (ref "J4") (pin "4") (pinfunction "4_4") (pintype "bidirectional"))
      (node (ref "TF1") (pin "3") (pinfunction "DI/CMD_3") (pintype "bidirectional"))
      (node (ref "U1") (pin "15") (pinfunction "PB3(PCINT3/OC2A/MOSI)_15") (pintype "bidirectional"))
    )
    (net (code "38") (name "/PB4{slash}MISO") (class "Default")
      (node (ref "ICSP") (pin "1") (pinfunction "1_1") (pintype "bidirectional"))
      (node (ref "J4") (pin "5") (pinfunction "5_5") (pintype "bidirectional"))
      (node (ref "R7") (pin "2") (pinfunction "2_2") (pintype "passive"))
      (node (ref "U1") (pin "16") (pinfunction "PB4(PCINT4/MISO)_16") (pintype "bidirectional"))
    )
    (net (code "39") (name "/PB5{slash}SCK") (class "Default")
      (node (ref "D13_LED") (pin "1") (pinfunction "1_1") (pintype "bidirectional"))
      (node (ref "D13_LED") (pin "2") (pinfunction "2_2") (pintype "bidirectional"))
      (node (ref "ICSP") (pin "2") (pinfunction "2_2") (pintype "bidirectional"))
      (node (ref "J4") (pin "6") (pinfunction "6_6") (pintype "bidirectional"))
      (node (ref "R5") (pin "1") (pinfunction "1_1") (pintype "passive"))
      (node (ref "TF1") (pin "5") (pinfunction "CLK_5") (pintype "bidirectional"))
      (node (ref "U1") (pin "17") (pinfunction "PB5(SCK/PCINT5)_17") (pintype "bidirectional"))
    )
    (net (code "40") (name "/PC0") (class "Default")
      (node (ref "J3") (pin "1") (pinfunction "1_1") (pintype "bidirectional"))
      (node (ref "U1") (pin "23") (pinfunction "PC0(ADC0/PCINT8)_23") (pintype "bidirectional"))
    )
    (net (code "41") (name "/PC1") (class "Default")
      (node (ref "J3") (pin "2") (pinfunction "2_2") (pintype "bidirectional"))
      (node (ref "U1") (pin "24") (pinfunction "PC1(ADC1/PCINT9)_24") (pintype "bidirectional"))
    )
    (net (code "42") (name "/PC2") (class "Default")
      (node (ref "J3") (pin "3") (pinfunction "3_3") (pintype "bidirectional"))
      (node (ref "U1") (pin "25") (pinfunction "PC2(ADC2/PCINT10)_25") (pintype "bidirectional"))
    )
    (net (code "43") (name "/PC3") (class "Default")
      (node (ref "J3") (pin "4") (pinfunction "4_4") (pintype "bidirectional"))
      (node (ref "U1") (pin "26") (pinfunction "PC3(ADC3/PCINT11)_26") (pintype "bidirectional"))
    )
    (net (code "44") (name "/PC4{slash}SDA") (class "Default")
      (node (ref "J3") (pin "5") (pinfunction "5_5") (pintype "bidirectional"))
      (node (ref "J4") (pin "9") (pinfunction "9_9") (pintype "bidirectional"))
      (node (ref "Q4") (pin "2") (pinfunction "S_2") (pintype "passive"))
      (node (ref "R9") (pin "2") (pinfunction "2_2") (pintype "passive"))
      (node (ref "U1") (pin "27") (pinfunction "PC4(ADC4/SDA/PCINT12)_27") (pintype "bidirectional"))
      (node (ref "U2") (pin "5") (pinfunction "SDA_5") (pintype "bidirectional"))
    )
    (net (code "45") (name "/PC5{slash}SCL") (class "Default")
      (node (ref "J3") (pin "6") (pinfunction "6_6") (pintype "bidirectional"))
      (node (ref "J4") (pin "10") (pinfunction "10_10") (pintype "bidirectional"))
      (node (ref "Q5") (pin "2") (pinfunction "S_2") (pintype "passive"))
      (node (ref "R20") (pin "1") (pinfunction "1_1") (pintype "passive"))
      (node (ref "U1") (pin "28") (pinfunction "PC5(ADC5/SCL/PCINT13)_28") (pintype "bidirectional"))
      (node (ref "U2") (pin "6") (pinfunction "SCL_6") (pintype "bidirectional"))
    )
    (net (code "46") (name "/PD0{slash}RXD") (class "Default")
      (node (ref "J2") (pin "3") (pinfunction "3_3") (pintype "bidirectional"))
      (node (ref "J5") (pin "1") (pinfunction "1_1") (pintype "bidirectional"))
      (node (ref "P6") (pin "11") (pinfunction "R_11") (pintype "bidirectional"))
      (node (ref "P6") (pin "MM") (pinfunction "C_MM") (pintype "bidirectional"))
      (node (ref "R15") (pin "1") (pinfunction "1_1") (pintype "passive"))
      (node (ref "U1") (pin "30") (pinfunction "PD0(RXD/PCINT16)_30") (pintype "bidirectional"))
    )
    (net (code "47") (name "/PD1{slash}TXD") (class "Default")
      (node (ref "J2") (pin "2") (pinfunction "2_2") (pintype "bidirectional"))
      (node (ref "J5") (pin "2") (pinfunction "2_2") (pintype "bidirectional"))
      (node (ref "P5") (pin "11") (pinfunction "R_11") (pintype "bidirectional"))
      (node (ref "P5") (pin "MM") (pinfunction "C_MM") (pintype "bidirectional"))
      (node (ref "R16") (pin "1") (pinfunction "1_1") (pintype "passive"))
      (node (ref "U1") (pin "31") (pinfunction "PD1(TXD/PCINT17)_31") (pintype "bidirectional"))
    )
    (net (code "48") (name "/PD2") (class "Default")
      (node (ref "J5") (pin "3") (pinfunction "3_3") (pintype "bidirectional"))
      (node (ref "P3") (pin "2") (pinfunction "2_2") (pintype "bidirectional"))
      (node (ref "U1") (pin "32") (pinfunction "PD2(INT0/PCINT18)_32") (pintype "bidirectional"))
    )
    (net (code "49") (name "/PD3") (class "Default")
      (node (ref "J5") (pin "4") (pinfunction "4_4") (pintype "bidirectional"))
      (node (ref "P4") (pin "2") (pinfunction "2_2") (pintype "bidirectional"))
      (node (ref "U1") (pin "1") (pinfunction "PD3(PCINT19/OC2B/INT1)_1") (pintype "bidirectional"))
    )
    (net (code "50") (name "/PD4") (class "Default")
      (node (ref "J5") (pin "5") (pinfunction "5_5") (pintype "bidirectional"))
      (node (ref "P2") (pin "2") (pinfunction "2_2") (pintype "bidirectional"))
      (node (ref "U1") (pin "2") (pinfunction "PD4(PCINT20/XCK/T0)_2") (pintype "bidirectional"))
    )
    (net (code "51") (name "/PD5") (class "Default")
      (node (ref "J5") (pin "6") (pinfunction "6_6") (pintype "bidirectional"))
      (node (ref "P1") (pin "2") (pinfunction "2_2") (pintype "bidirectional"))
      (node (ref "U1") (pin "9") (pinfunction "PD5(PCINT21/OC0B/T1)_9") (pintype "bidirectional"))
    )
    (net (code "52") (name "/PD6") (class "Default")
      (node (ref "J5") (pin "7") (pinfunction "7_7") (pintype "bidirectional"))
      (node (ref "P6") (pin "00") (pinfunction "L_00") (pintype "bidirectional"))
      (node (ref "U1") (pin "10") (pinfunction "PD6(PCINT22/OC0A/AIN0)_10") (pintype "bidirectional"))
    )
    (net (code "53") (name "/PD7") (class "Default")
      (node (ref "J5") (pin "8") (pinfunction "8_8") (pintype "bidirectional"))
      (node (ref "P5") (pin "00") (pinfunction "L_00") (pintype "bidirectional"))
      (node (ref "R4") (pin "1") (pinfunction "1_1") (pintype "passive"))
      (node (ref "U1") (pin "11") (pinfunction "PD7(PCINT23/AIN1)_11") (pintype "bidirectional"))
    )
    (net (code "54") (name "/SD_SO") (class "Default")
      (node (ref "TF1") (pin "7") (pinfunction "DO/D0_7") (pintype "bidirectional"))
      (node (ref "U4") (pin "2") (pinfunction "A_2") (pintype "bidirectional"))
    )
    (net (code "55") (name "/TF_3V3") (class "Default")
      (node (ref "C12") (pin "2") (pinfunction "2_2") (pintype "passive"))
      (node (ref "Q2") (pin "3") (pinfunction "D_3") (pintype "passive"))
      (node (ref "TF1") (pin "4") (pinfunction "VDD_4") (pintype "bidirectional"))
    )
    (net (code "56") (name "/USB5V") (class "Default")
      (node (ref "D2") (pin "1") (pinfunction "+_1") (pintype "passive"))
      (node (ref "D5") (pin "1") (pinfunction "+_1") (pintype "passive"))
      (node (ref "ICSP") (pin "6") (pinfunction "6_6") (pintype "bidirectional"))
      (node (ref "J2") (pin "4") (pinfunction "4_4") (pintype "bidirectional"))
      (node (ref "Q3") (pin "1") (pinfunction "G_1") (pintype "passive"))
      (node (ref "R24") (pin "2") (pinfunction "2_2") (pintype "passive"))
    )
    (net (code "57") (name "/VCC") (class "Default")
      (node (ref "C10") (pin "2") (pinfunction "2_2") (pintype "passive"))
      (node (ref "D5") (pin "2") (pinfunction "-_2") (pintype "passive"))
      (node (ref "D7,8") (pin "3") (pinfunction "3_3") (pintype "bidirectional"))
      (node (ref "I2C") (pin "3") (pinfunction "3_3") (pintype "bidirectional"))
      (node (ref "J1") (pin "4") (pinfunction "4_4") (pintype "bidirectional"))
      (node (ref "Q3") (pin "2") (pinfunction "S_2") (pintype "passive"))
      (node (ref "R1") (pin "2") (pinfunction "2_2") (pintype "passive"))
      (node (ref "R21") (pin "2") (pinfunction "2_2") (pintype "passive"))
      (node (ref "U3") (pin "1") (pinfunction "RUN_1") (pintype "bidirectional"))
      (node (ref "U3") (pin "4") (pinfunction "VIN_4") (pintype "input"))
    )
    (net (code "58") (name "/V_REF") (class "Default")
      (node (ref "C2") (pin "2") (pinfunction "2_2") (pintype "passive"))
      (node (ref "J4") (pin "8") (pinfunction "8_8") (pintype "bidirectional"))
      (node (ref "U1") (pin "20") (pinfunction "AREF_20") (pintype "bidirectional"))
    )
    (net (code "59") (name "/XTAL1") (class "Default")
      (node (ref "C6") (pin "2") (pinfunction "2_2") (pintype "passive"))
      (node (ref "U1") (pin "7") (pinfunction "PB6(PCINT6/XTAL1/TOSC1)_7") (pintype "bidirectional"))
      (node (ref "X3") (pin "2") (pinfunction "2_2") (pintype "passive"))
    )
    (net (code "60") (name "/XTAL2") (class "Default")
      (node (ref "C7") (pin "2") (pinfunction "2_2") (pintype "passive"))
      (node (ref "U1") (pin "8") (pinfunction "PB7(PCINT7/XTAL2/TOSC2)_8") (pintype "bidirectional"))
      (node (ref "X3") (pin "1") (pinfunction "1_1") (pintype "passive"))
    )
    (net (code "61") (name "/~{INTA}") (class "Default")
      (node (ref "P3") (pin "1") (pinfunction "1_1") (pintype "bidirectional"))
      (node (ref "U2") (pin "3") (pinfunction "~{INTA}_3") (pintype "bidirectional"))
    )
    (net (code "62") (name "/~{INTB}") (class "Default")
      (node (ref "P4") (pin "1") (pinfunction "1_1") (pintype "bidirectional"))
      (node (ref "U2") (pin "7") (pinfunction "SQW/~{INTB}_7") (pintype "bidirectional"))
    )
    (net (code "63") (name "GND_POWER") (class "Default")
      (node (ref "BAT1") (pin "-") (pinfunction "-_-") (pintype "bidirectional"))
      (node (ref "BEE") (pin "10") (pinfunction "GND_10") (pintype "bidirectional"))
      (node (ref "BEE_RST") (pin "2") (pinfunction "B0_2") (pintype "bidirectional"))
      (node (ref "BEE_RST") (pin "3") (pinfunction "B1_3") (pintype "bidirectional"))
      (node (ref "C10") (pin "1") (pinfunction "1_1") (pintype "passive"))
      (node (ref "C11") (pin "2") (pinfunction "2_2") (pintype "passive"))
      (node (ref "C12") (pin "1") (pinfunction "1_1") (pintype "passive"))
      (node (ref "C13") (pin "1") (pinfunction "1_1") (pintype "passive"))
      (node (ref "C14") (pin "-") (pinfunction "-_-") (pintype "passive"))
      (node (ref "C15") (pin "2") (pinfunction "2_2") (pintype "passive"))
      (node (ref "C2") (pin "1") (pinfunction "1_1") (pintype "passive"))
      (node (ref "C20") (pin "1") (pinfunction "1_1") (pintype "passive"))
      (node (ref "C3") (pin "1") (pinfunction "1_1") (pintype "passive"))
      (node (ref "C5") (pin "2") (pinfunction "2_2") (pintype "passive"))
      (node (ref "C6") (pin "1") (pinfunction "1_1") (pintype "passive"))
      (node (ref "C7") (pin "1") (pinfunction "1_1") (pintype "passive"))
      (node (ref "C8") (pin "1") (pinfunction "1_1") (pintype "passive"))
      (node (ref "C9") (pin "-") (pinfunction "-_-") (pintype "passive"))
      (node (ref "D7,8") (pin "4") (pinfunction "4_4") (pintype "bidirectional"))
      (node (ref "I2C") (pin "4") (pinfunction "4_4") (pintype "bidirectional"))
      (node (ref "ICSP") (pin "4") (pinfunction "4_4") (pintype "bidirectional"))
      (node (ref "J1") (pin "2") (pinfunction "2_2") (pintype "bidirectional"))
      (node (ref "J1") (pin "3") (pinfunction "3_3") (pintype "bidirectional"))
      (node (ref "J2") (pin "5") (pinfunction "5_5") (pintype "bidirectional"))
      (node (ref "J2") (pin "6") (pinfunction "6_6") (pintype "bidirectional"))
      (node (ref "J4") (pin "7") (pinfunction "7_7") (pintype "bidirectional"))
      (node (ref "J6") (pin "10") (pinfunction "10_10") (pintype "bidirectional"))
      (node (ref "LIPO_BAT") (pin "2") (pinfunction "P$2_2") (pintype "bidirectional"))
      (node (ref "PB0") (pin "-") (pinfunction "-_-") (pintype "passive"))
      (node (ref "R10") (pin "1") (pinfunction "1_1") (pintype "passive"))
      (node (ref "R13") (pin "2") (pinfunction "2_2") (pintype "passive"))
      (node (ref "R2") (pin "1") (pinfunction "1_1") (pintype "passive"))
      (node (ref "R24") (pin "1") (pinfunction "1_1") (pintype "passive"))
      (node (ref "R26") (pin "1") (pinfunction "1_1") (pintype "passive"))
      (node (ref "R27") (pin "1") (pinfunction "1_1") (pintype "passive"))
      (node (ref "RSSI") (pin "-") (pinfunction "-_-") (pintype "passive"))
      (node (ref "RST") (pin "2") (pinfunction "B0_2") (pintype "bidirectional"))
      (node (ref "RST") (pin "3") (pinfunction "B1_3") (pintype "bidirectional"))
      (node (ref "SOLAR") (pin "2") (pinfunction "P$2_2") (pintype "bidirectional"))
      (node (ref "TF1") (pin "6") (pinfunction "VSS_6") (pintype "bidirectional"))
      (node (ref "TF1") (pin "GND@1") (pinfunction "GND_GND@1") (pintype "bidirectional"))
      (node (ref "TF1") (pin "GND@2") (pinfunction "GND_GND@2") (pintype "bidirectional"))
      (node (ref "TF1") (pin "GND@3") (pinfunction "GND_GND@3") (pintype "bidirectional"))
      (node (ref "TF1") (pin "GND@4") (pinfunction "GND_GND@4") (pintype "bidirectional"))
      (node (ref "U1") (pin "21") (pinfunction "GND3_21") (pintype "bidirectional"))
      (node (ref "U1") (pin "3") (pinfunction "GND1_3") (pintype "bidirectional"))
      (node (ref "U1") (pin "5") (pinfunction "GND2_5") (pintype "bidirectional"))
      (node (ref "U2") (pin "4") (pinfunction "GND_4") (pintype "bidirectional"))
      (node (ref "U3") (pin "2") (pinfunction "GND_2") (pintype "power_in"))
      (node (ref "U4") (pin "3") (pinfunction "GND_3") (pintype "bidirectional"))
      (node (ref "U5") (pin "1") (pinfunction "TEMP_1") (pintype "input"))
      (node (ref "U5") (pin "3") (pinfunction "GND_3") (pintype "power_in"))
    )
    (net (code "64") (name "Net-(CH-Pad+)") (class "Default")
      (node (ref "CH") (pin "+") (pinfunction "+_+") (pintype "passive"))
      (node (ref "OK") (pin "+") (pinfunction "+_+") (pintype "passive"))
      (node (ref "R6") (pin "1") (pinfunction "1_1") (pintype "passive"))
    )
    (net (code "65") (name "Net-(D1-+)") (class "Default")
      (node (ref "D1") (pin "1") (pinfunction "+_1") (pintype "passive"))
      (node (ref "SOLAR") (pin "1") (pinfunction "P$1_1") (pintype "bidirectional"))
    )
    (net (code "66") (name "Net-(D3-+)") (class "Default")
      (node (ref "BAT1") (pin "+") (pinfunction "+_+") (pintype "bidirectional"))
      (node (ref "D3") (pin "1") (pinfunction "+_1") (pintype "passive"))
    )
    (net (code "67") (name "Net-(D3--)") (class "Default")
      (node (ref "D3") (pin "2") (pinfunction "-_2") (pintype "passive"))
      (node (ref "D4") (pin "2") (pinfunction "-_2") (pintype "passive"))
      (node (ref "U2") (pin "8") (pinfunction "VCC_8") (pintype "bidirectional"))
    )
    (net (code "68") (name "Net-(L1-Pad2)") (class "Default")
      (node (ref "L1") (pin "2") (pinfunction "2_2") (pintype "passive"))
      (node (ref "L2") (pin "1") (pinfunction "1_1") (pintype "passive"))
    )
    (net (code "69") (name "Net-(PB0-Pad+)") (class "Default")
      (node (ref "PB0") (pin "+") (pinfunction "+_+") (pintype "passive"))
      (node (ref "R5") (pin "2") (pinfunction "2_2") (pintype "passive"))
    )
    (net (code "70") (name "Net-(Q2-G)") (class "Default")
      (node (ref "P2") (pin "1") (pinfunction "1_1") (pintype "bidirectional"))
      (node (ref "Q2") (pin "1") (pinfunction "G_1") (pintype "passive"))
      (node (ref "R26") (pin "2") (pinfunction "2_2") (pintype "passive"))
    )
    (net (code "71") (name "Net-(Q6-G)") (class "Default")
      (node (ref "P1") (pin "1") (pinfunction "1_1") (pintype "bidirectional"))
      (node (ref "Q6") (pin "1") (pinfunction "G_1") (pintype "passive"))
      (node (ref "R2") (pin "2") (pinfunction "2_2") (pintype "passive"))
    )
    (net (code "72") (name "Net-(R17-Pad1)") (class "Default")
      (node (ref "R17") (pin "1") (pinfunction "1_1") (pintype "passive"))
      (node (ref "RSSI") (pin "+") (pinfunction "+_+") (pintype "passive"))
    )
    (net (code "73") (name "Net-(U2-X1)") (class "Default")
      (node (ref "U2") (pin "1") (pinfunction "X1_1") (pintype "bidirectional"))
      (node (ref "X2") (pin "2") (pinfunction "2_2") (pintype "passive"))
    )
    (net (code "74") (name "Net-(U2-X2)") (class "Default")
      (node (ref "U2") (pin "2") (pinfunction "X2_2") (pintype "bidirectional"))
      (node (ref "X2") (pin "1") (pinfunction "1_1") (pintype "passive"))
    )
    (net (code "75") (name "Net-(U3-SW)") (class "Default")
      (node (ref "L1") (pin "1") (pinfunction "1_1") (pintype "passive"))
      (node (ref "U3") (pin "3") (pinfunction "SW_3") (pintype "bidirectional"))
    )
    (net (code "76") (name "Net-(U3-VFB)") (class "Default")
      (node (ref "C4") (pin "1") (pinfunction "1_1") (pintype "passive"))
      (node (ref "R27") (pin "2") (pinfunction "2_2") (pintype "passive"))
      (node (ref "R3") (pin "1") (pinfunction "1_1") (pintype "passive"))
      (node (ref "U3") (pin "5") (pinfunction "VFB_5") (pintype "input"))
    )
    (net (code "77") (name "Net-(U4-Y)") (class "Default")
      (node (ref "R7") (pin "1") (pinfunction "1_1") (pintype "passive"))
      (node (ref "U4") (pin "4") (pinfunction "Y_4") (pintype "bidirectional"))
    )
    (net (code "78") (name "Net-(U5-ISET)") (class "Default")
      (node (ref "R10") (pin "2") (pinfunction "2_2") (pintype "passive"))
      (node (ref "U5") (pin "2") (pinfunction "ISET_2") (pintype "bidirectional"))
    )
    (net (code "79") (name "unconnected-(J1-Pad1)") (class "Default")
      (node (ref "J1") (pin "1") (pinfunction "1_1") (pintype "bidirectional"))
    )
    (net (code "80") (name "unconnected-(J1-Pad8)") (class "Default")
      (node (ref "J1") (pin "8") (pinfunction "8_8") (pintype "bidirectional"))
    )
    (net (code "81") (name "unconnected-(TF1-RSV{slash}D1-Pad8)") (class "Default")
      (node (ref "TF1") (pin "8") (pinfunction "RSV/D1_8") (pintype "bidirectional"))
    )
    (net (code "82") (name "unconnected-(TF1-RSV{slash}D2-Pad1)") (class "Default")
      (node (ref "TF1") (pin "1") (pinfunction "RSV/D2_1") (pintype "bidirectional"))
    )
  )
)
